# Upper.net
KiCad netlist of a schematic drawn in Altium Designer
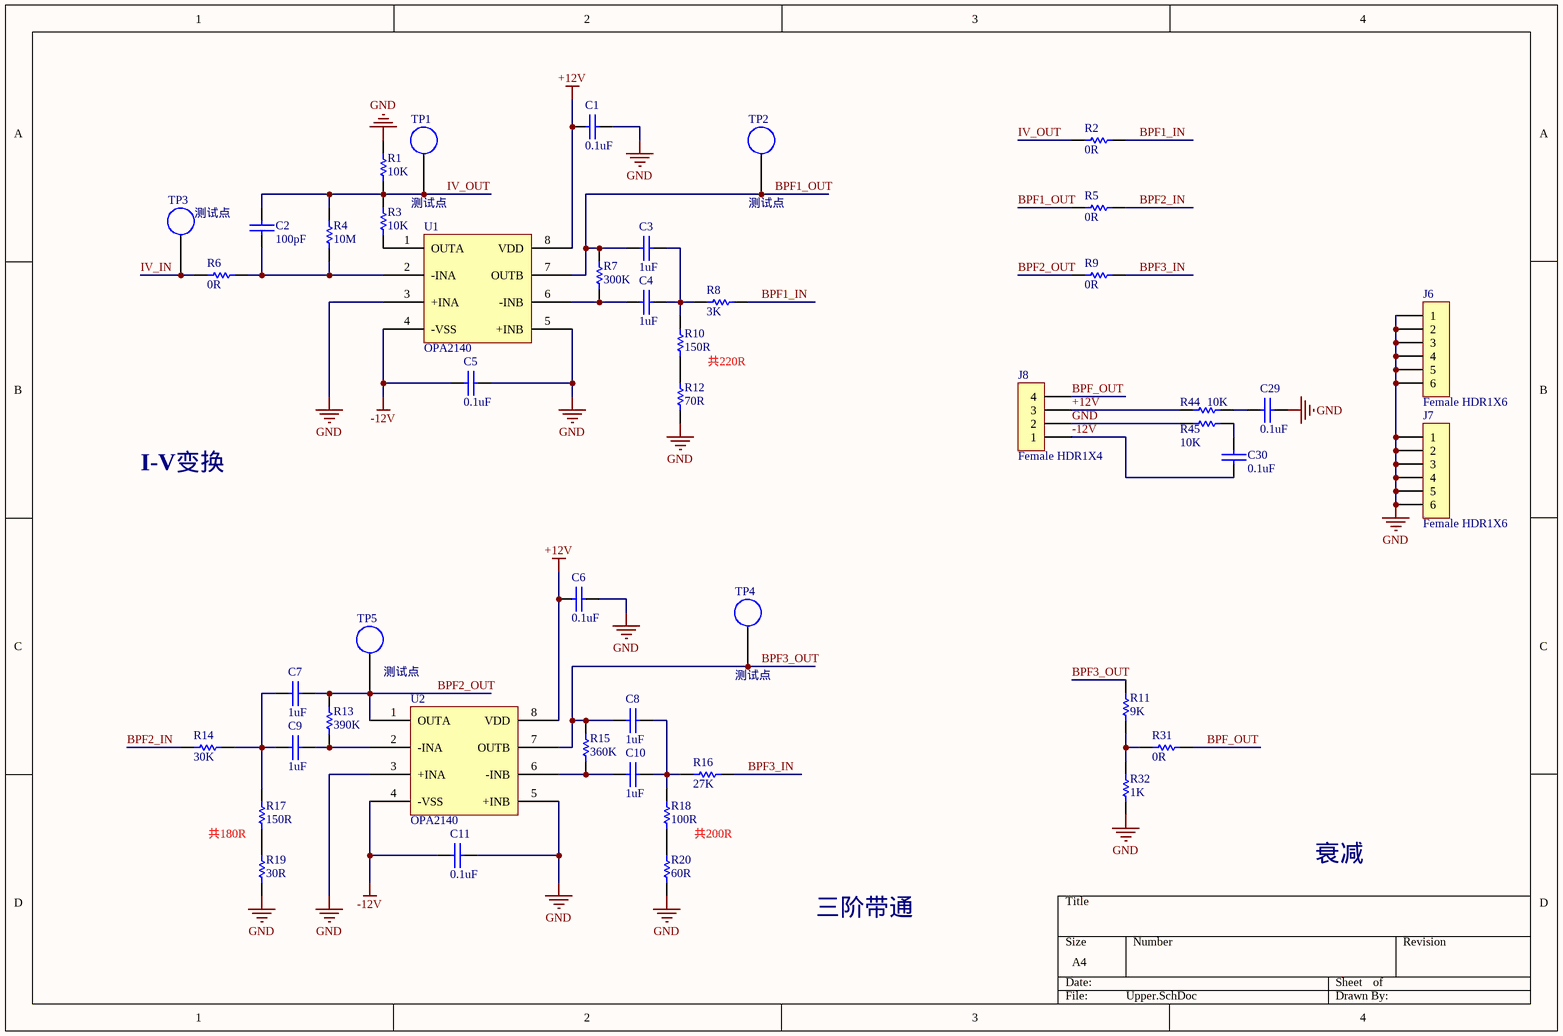
[diagram p0: Upper.SchDoc]

(export (version "E")
  (design (tool "Eeschema 10.0.6"))
  (components
    (comp (ref "C1")
      (value "0.1uF")
      (footprint "0603C")
      (description "无极性电容")
      (libsource (lib "电容") (part "CAP"))
    )
    (comp (ref "C2")
      (value "100pF")
      (footprint "0603C")
      (description "无极性电容")
      (libsource (lib "电容") (part "CAP"))
    )
    (comp (ref "C3")
      (value "1uF")
      (footprint "1206C")
      (description "无极性电容")
      (libsource (lib "电容") (part "CAP"))
    )
    (comp (ref "C4")
      (value "1uF")
      (footprint "1206C")
      (description "无极性电容")
      (libsource (lib "电容") (part "CAP"))
    )
    (comp (ref "C5")
      (value "0.1uF")
      (footprint "0603C")
      (description "无极性电容")
      (libsource (lib "电容") (part "CAP"))
    )
    (comp (ref "C6")
      (value "0.1uF")
      (footprint "0603C")
      (description "无极性电容")
      (libsource (lib "电容") (part "CAP"))
    )
    (comp (ref "C7")
      (value "1uF")
      (footprint "1206C")
      (description "无极性电容")
      (libsource (lib "电容") (part "CAP"))
    )
    (comp (ref "C8")
      (value "1uF")
      (footprint "1206C")
      (description "无极性电容")
      (libsource (lib "电容") (part "CAP"))
    )
    (comp (ref "C9")
      (value "1uF")
      (footprint "1206C")
      (description "无极性电容")
      (libsource (lib "电容") (part "CAP"))
    )
    (comp (ref "C10")
      (value "1uF")
      (footprint "1206C")
      (description "无极性电容")
      (libsource (lib "电容") (part "CAP"))
    )
    (comp (ref "C11")
      (value "0.1uF")
      (footprint "0603C")
      (description "无极性电容")
      (libsource (lib "电容") (part "CAP"))
    )
    (comp (ref "C29")
      (value "0.1uF")
      (footprint "0603C")
      (description "无极性电容")
      (libsource (lib "电容") (part "CAP"))
    )
    (comp (ref "C30")
      (value "0.1uF")
      (footprint "0603C")
      (description "无极性电容")
      (libsource (lib "电容") (part "CAP"))
    )
    (comp (ref "J6")
      (value "Female HDR1X6")
      (footprint "Fe-HDR1X6/2.54-S")
      (libsource (lib "排母") (part "Female HDR1X6"))
    )
    (comp (ref "J7")
      (value "Female HDR1X6")
      (footprint "Fe-HDR1X6/2.54-S")
      (libsource (lib "排母") (part "Female HDR1X6"))
    )
    (comp (ref "J8")
      (value "Female HDR1X4")
      (footprint "Fe-HDR1X4/2.54-S")
      (libsource (lib "排母") (part "Female HDR1X4"))
    )
    (comp (ref "R1") (value "10K") (footprint "0603R") (libsource (lib "电阻") (part "RES")))
    (comp (ref "R2") (value "0R") (footprint "0603R") (libsource (lib "电阻") (part "RES")))
    (comp (ref "R3") (value "10K") (footprint "0603R") (libsource (lib "电阻") (part "RES")))
    (comp (ref "R4") (value "10M") (footprint "0603R") (libsource (lib "电阻") (part "RES")))
    (comp (ref "R5") (value "0R") (footprint "0603R") (libsource (lib "电阻") (part "RES")))
    (comp (ref "R6") (value "0R") (footprint "0603R") (libsource (lib "电阻") (part "RES")))
    (comp (ref "R7") (value "300K") (footprint "0603R") (libsource (lib "电阻") (part "RES")))
    (comp (ref "R8") (value "3K") (footprint "0603R") (libsource (lib "电阻") (part "RES")))
    (comp (ref "R9") (value "0R") (footprint "0603R") (libsource (lib "电阻") (part "RES")))
    (comp (ref "R10") (value "150R") (footprint "0603R") (libsource (lib "电阻") (part "RES")))
    (comp (ref "R11") (value "9K") (footprint "0603R") (libsource (lib "电阻") (part "RES")))
    (comp (ref "R12") (value "70R") (footprint "0603R") (libsource (lib "电阻") (part "RES")))
    (comp (ref "R13") (value "390K") (footprint "0603R") (libsource (lib "电阻") (part "RES")))
    (comp (ref "R14") (value "30K") (footprint "0603R") (libsource (lib "电阻") (part "RES")))
    (comp (ref "R15") (value "360K") (footprint "0603R") (libsource (lib "电阻") (part "RES")))
    (comp (ref "R16") (value "27K") (footprint "0603R") (libsource (lib "电阻") (part "RES")))
    (comp (ref "R17") (value "150R") (footprint "0603R") (libsource (lib "电阻") (part "RES")))
    (comp (ref "R18") (value "100R") (footprint "0603R") (libsource (lib "电阻") (part "RES")))
    (comp (ref "R19") (value "30R") (footprint "0603R") (libsource (lib "电阻") (part "RES")))
    (comp (ref "R20") (value "60R") (footprint "0603R") (libsource (lib "电阻") (part "RES")))
    (comp (ref "R31") (value "0R") (footprint "0603R") (libsource (lib "电阻") (part "RES")))
    (comp (ref "R32") (value "1K") (footprint "0603R") (libsource (lib "电阻") (part "RES")))
    (comp (ref "R44") (value "10K") (footprint "0603R") (libsource (lib "电阻") (part "RES")))
    (comp (ref "R45") (value "10K") (footprint "0603R") (libsource (lib "电阻") (part "RES")))
    (comp (ref "TP1") (value "测试点") (footprint "TP") (libsource (lib "固定柱和测试点") (part "测试点")))
    (comp (ref "TP2") (value "测试点") (footprint "TP") (libsource (lib "固定柱和测试点") (part "测试点")))
    (comp (ref "TP3") (value "测试点") (footprint "TP") (libsource (lib "固定柱和测试点") (part "测试点")))
    (comp (ref "TP4") (value "测试点") (footprint "TP") (libsource (lib "固定柱和测试点") (part "测试点")))
    (comp (ref "TP5") (value "测试点") (footprint "TP") (libsource (lib "固定柱和测试点") (part "测试点")))
    (comp (ref "U1") (value "OPA2140") (footprint "SOP8") (libsource (lib "未分类IC") (part "NE5532")))
    (comp (ref "U2") (value "OPA2140") (footprint "SOP8") (libsource (lib "未分类IC") (part "NE5532")))
  )
  (nets
    (net (code "1") (name "+12V") (class "Default")
      (node (ref "C1") (pin "1") (pinfunction "1_1") (pintype "passive"))
      (node (ref "C6") (pin "1") (pinfunction "1_1") (pintype "passive"))
      (node (ref "J8") (pin "3") (pinfunction "3_3") (pintype "passive"))
      (node (ref "R44") (pin "2") (pinfunction "2_2") (pintype "passive"))
      (node (ref "U1") (pin "8") (pinfunction "VDD_8") (pintype "passive"))
      (node (ref "U2") (pin "8") (pinfunction "VDD_8") (pintype "passive"))
    )
    (net (code "2") (name "-12V") (class "Default")
      (node (ref "C11") (pin "1") (pinfunction "1_1") (pintype "passive"))
      (node (ref "C30") (pin "1") (pinfunction "1_1") (pintype "passive"))
      (node (ref "C5") (pin "1") (pinfunction "1_1") (pintype "passive"))
      (node (ref "J8") (pin "1") (pinfunction "1_1") (pintype "passive"))
      (node (ref "U1") (pin "4") (pinfunction "-VSS_4") (pintype "passive"))
      (node (ref "U2") (pin "4") (pinfunction "-VSS_4") (pintype "passive"))
    )
    (net (code "3") (name "/BPF1_IN") (class "Default")
      (node (ref "R2") (pin "2") (pinfunction "2_2") (pintype "passive"))
      (node (ref "R8") (pin "1") (pinfunction "1_1") (pintype "passive"))
    )
    (net (code "4") (name "/BPF1_OUT") (class "Default")
      (node (ref "C3") (pin "2") (pinfunction "2_2") (pintype "passive"))
      (node (ref "R5") (pin "1") (pinfunction "1_1") (pintype "passive"))
      (node (ref "R7") (pin "2") (pinfunction "2_2") (pintype "passive"))
      (node (ref "TP2") (pin "1") (pinfunction "TP_1") (pintype "passive"))
      (node (ref "U1") (pin "7") (pinfunction "OUTB_7") (pintype "passive"))
    )
    (net (code "5") (name "/BPF2_IN") (class "Default")
      (node (ref "R14") (pin "2") (pinfunction "2_2") (pintype "passive"))
      (node (ref "R5") (pin "2") (pinfunction "2_2") (pintype "passive"))
    )
    (net (code "6") (name "/BPF2_OUT") (class "Default")
      (node (ref "C7") (pin "1") (pinfunction "1_1") (pintype "passive"))
      (node (ref "R13") (pin "2") (pinfunction "2_2") (pintype "passive"))
      (node (ref "R9") (pin "1") (pinfunction "1_1") (pintype "passive"))
      (node (ref "TP5") (pin "1") (pinfunction "TP_1") (pintype "passive"))
      (node (ref "U2") (pin "1") (pinfunction "OUTA_1") (pintype "passive"))
    )
    (net (code "7") (name "/BPF3_IN") (class "Default")
      (node (ref "R16") (pin "1") (pinfunction "1_1") (pintype "passive"))
      (node (ref "R9") (pin "2") (pinfunction "2_2") (pintype "passive"))
    )
    (net (code "8") (name "/BPF3_OUT") (class "Default")
      (node (ref "C8") (pin "2") (pinfunction "2_2") (pintype "passive"))
      (node (ref "R11") (pin "2") (pinfunction "2_2") (pintype "passive"))
      (node (ref "R15") (pin "2") (pinfunction "2_2") (pintype "passive"))
      (node (ref "TP4") (pin "1") (pinfunction "TP_1") (pintype "passive"))
      (node (ref "U2") (pin "7") (pinfunction "OUTB_7") (pintype "passive"))
    )
    (net (code "9") (name "/BPF_OUT") (class "Default")
      (node (ref "J8") (pin "4") (pinfunction "4_4") (pintype "passive"))
      (node (ref "R31") (pin "1") (pinfunction "1_1") (pintype "passive"))
    )
    (net (code "10") (name "/IV_IN") (class "Default")
      (node (ref "R6") (pin "2") (pinfunction "2_2") (pintype "passive"))
      (node (ref "TP3") (pin "1") (pinfunction "TP_1") (pintype "passive"))
    )
    (net (code "11") (name "/IV_OUT") (class "Default")
      (node (ref "C2") (pin "1") (pinfunction "1_1") (pintype "passive"))
      (node (ref "R1") (pin "1") (pinfunction "1_1") (pintype "passive"))
      (node (ref "R2") (pin "1") (pinfunction "1_1") (pintype "passive"))
      (node (ref "R3") (pin "2") (pinfunction "2_2") (pintype "passive"))
      (node (ref "R4") (pin "2") (pinfunction "2_2") (pintype "passive"))
      (node (ref "TP1") (pin "1") (pinfunction "TP_1") (pintype "passive"))
    )
    (net (code "12") (name "GND") (class "Default")
      (node (ref "C1") (pin "2") (pinfunction "2_2") (pintype "passive"))
      (node (ref "C11") (pin "2") (pinfunction "2_2") (pintype "passive"))
      (node (ref "C29") (pin "1") (pinfunction "1_1") (pintype "passive"))
      (node (ref "C5") (pin "2") (pinfunction "2_2") (pintype "passive"))
      (node (ref "C6") (pin "2") (pinfunction "2_2") (pintype "passive"))
      (node (ref "J6") (pin "1") (pinfunction "1_1") (pintype "passive"))
      (node (ref "J6") (pin "2") (pinfunction "2_2") (pintype "passive"))
      (node (ref "J6") (pin "3") (pinfunction "3_3") (pintype "passive"))
      (node (ref "J6") (pin "4") (pinfunction "4_4") (pintype "passive"))
      (node (ref "J6") (pin "5") (pinfunction "5_5") (pintype "passive"))
      (node (ref "J6") (pin "6") (pinfunction "6_6") (pintype "passive"))
      (node (ref "J7") (pin "1") (pinfunction "1_1") (pintype "passive"))
      (node (ref "J7") (pin "2") (pinfunction "2_2") (pintype "passive"))
      (node (ref "J7") (pin "3") (pinfunction "3_3") (pintype "passive"))
      (node (ref "J7") (pin "4") (pinfunction "4_4") (pintype "passive"))
      (node (ref "J7") (pin "5") (pinfunction "5_5") (pintype "passive"))
      (node (ref "J7") (pin "6") (pinfunction "6_6") (pintype "passive"))
      (node (ref "J8") (pin "2") (pinfunction "2_2") (pintype "passive"))
      (node (ref "R1") (pin "2") (pinfunction "2_2") (pintype "passive"))
      (node (ref "R12") (pin "2") (pinfunction "2_2") (pintype "passive"))
      (node (ref "R19") (pin "2") (pinfunction "2_2") (pintype "passive"))
      (node (ref "R20") (pin "2") (pinfunction "2_2") (pintype "passive"))
      (node (ref "R32") (pin "1") (pinfunction "1_1") (pintype "passive"))
      (node (ref "R45") (pin "2") (pinfunction "2_2") (pintype "passive"))
      (node (ref "U1") (pin "3") (pinfunction "+INA_3") (pintype "passive"))
      (node (ref "U1") (pin "5") (pinfunction "+INB_5") (pintype "passive"))
      (node (ref "U2") (pin "3") (pinfunction "+INA_3") (pintype "passive"))
      (node (ref "U2") (pin "5") (pinfunction "+INB_5") (pintype "passive"))
    )
    (net (code "13") (name "Net-(C3-Pad1)") (class "Default")
      (node (ref "C3") (pin "1") (pinfunction "1_1") (pintype "passive"))
      (node (ref "C4") (pin "2") (pinfunction "2_2") (pintype "passive"))
      (node (ref "R10") (pin "1") (pinfunction "1_1") (pintype "passive"))
      (node (ref "R8") (pin "2") (pinfunction "2_2") (pintype "passive"))
    )
    (net (code "14") (name "Net-(C7-Pad2)") (class "Default")
      (node (ref "C7") (pin "2") (pinfunction "2_2") (pintype "passive"))
      (node (ref "C9") (pin "1") (pinfunction "1_1") (pintype "passive"))
      (node (ref "R14") (pin "1") (pinfunction "1_1") (pintype "passive"))
      (node (ref "R17") (pin "1") (pinfunction "1_1") (pintype "passive"))
    )
    (net (code "15") (name "Net-(C10-Pad2)") (class "Default")
      (node (ref "C10") (pin "2") (pinfunction "2_2") (pintype "passive"))
      (node (ref "C8") (pin "1") (pinfunction "1_1") (pintype "passive"))
      (node (ref "R16") (pin "2") (pinfunction "2_2") (pintype "passive"))
      (node (ref "R18") (pin "1") (pinfunction "1_1") (pintype "passive"))
    )
    (net (code "16") (name "Net-(C29-Pad2)") (class "Default")
      (node (ref "C29") (pin "2") (pinfunction "2_2") (pintype "passive"))
      (node (ref "R44") (pin "1") (pinfunction "1_1") (pintype "passive"))
    )
    (net (code "17") (name "Net-(C30-Pad2)") (class "Default")
      (node (ref "C30") (pin "2") (pinfunction "2_2") (pintype "passive"))
      (node (ref "R45") (pin "1") (pinfunction "1_1") (pintype "passive"))
    )
    (net (code "18") (name "Net-(R10-Pad2)") (class "Default")
      (node (ref "R10") (pin "2") (pinfunction "2_2") (pintype "passive"))
      (node (ref "R12") (pin "1") (pinfunction "1_1") (pintype "passive"))
    )
    (net (code "19") (name "Net-(R11-Pad1)") (class "Default")
      (node (ref "R11") (pin "1") (pinfunction "1_1") (pintype "passive"))
      (node (ref "R31") (pin "2") (pinfunction "2_2") (pintype "passive"))
      (node (ref "R32") (pin "2") (pinfunction "2_2") (pintype "passive"))
    )
    (net (code "20") (name "Net-(R17-Pad2)") (class "Default")
      (node (ref "R17") (pin "2") (pinfunction "2_2") (pintype "passive"))
      (node (ref "R19") (pin "1") (pinfunction "1_1") (pintype "passive"))
    )
    (net (code "21") (name "Net-(R18-Pad2)") (class "Default")
      (node (ref "R18") (pin "2") (pinfunction "2_2") (pintype "passive"))
      (node (ref "R20") (pin "1") (pinfunction "1_1") (pintype "passive"))
    )
    (net (code "22") (name "Net-(U1--INA)") (class "Default")
      (node (ref "C2") (pin "2") (pinfunction "2_2") (pintype "passive"))
      (node (ref "R4") (pin "1") (pinfunction "1_1") (pintype "passive"))
      (node (ref "R6") (pin "1") (pinfunction "1_1") (pintype "passive"))
      (node (ref "U1") (pin "2") (pinfunction "-INA_2") (pintype "passive"))
    )
    (net (code "23") (name "Net-(U1--INB)") (class "Default")
      (node (ref "C4") (pin "1") (pinfunction "1_1") (pintype "passive"))
      (node (ref "R7") (pin "1") (pinfunction "1_1") (pintype "passive"))
      (node (ref "U1") (pin "6") (pinfunction "-INB_6") (pintype "passive"))
    )
    (net (code "24") (name "Net-(U1-OUTA)") (class "Default")
      (node (ref "R3") (pin "1") (pinfunction "1_1") (pintype "passive"))
      (node (ref "U1") (pin "1") (pinfunction "OUTA_1") (pintype "passive"))
    )
    (net (code "25") (name "Net-(U2--INA)") (class "Default")
      (node (ref "C9") (pin "2") (pinfunction "2_2") (pintype "passive"))
      (node (ref "R13") (pin "1") (pinfunction "1_1") (pintype "passive"))
      (node (ref "U2") (pin "2") (pinfunction "-INA_2") (pintype "passive"))
    )
    (net (code "26") (name "Net-(U2--INB)") (class "Default")
      (node (ref "C10") (pin "1") (pinfunction "1_1") (pintype "passive"))
      (node (ref "R15") (pin "1") (pinfunction "1_1") (pintype "passive"))
      (node (ref "U2") (pin "6") (pinfunction "-INB_6") (pintype "passive"))
    )
  )
)
